# Sheet1.net
KiCad netlist of a schematic drawn in Altium Designer
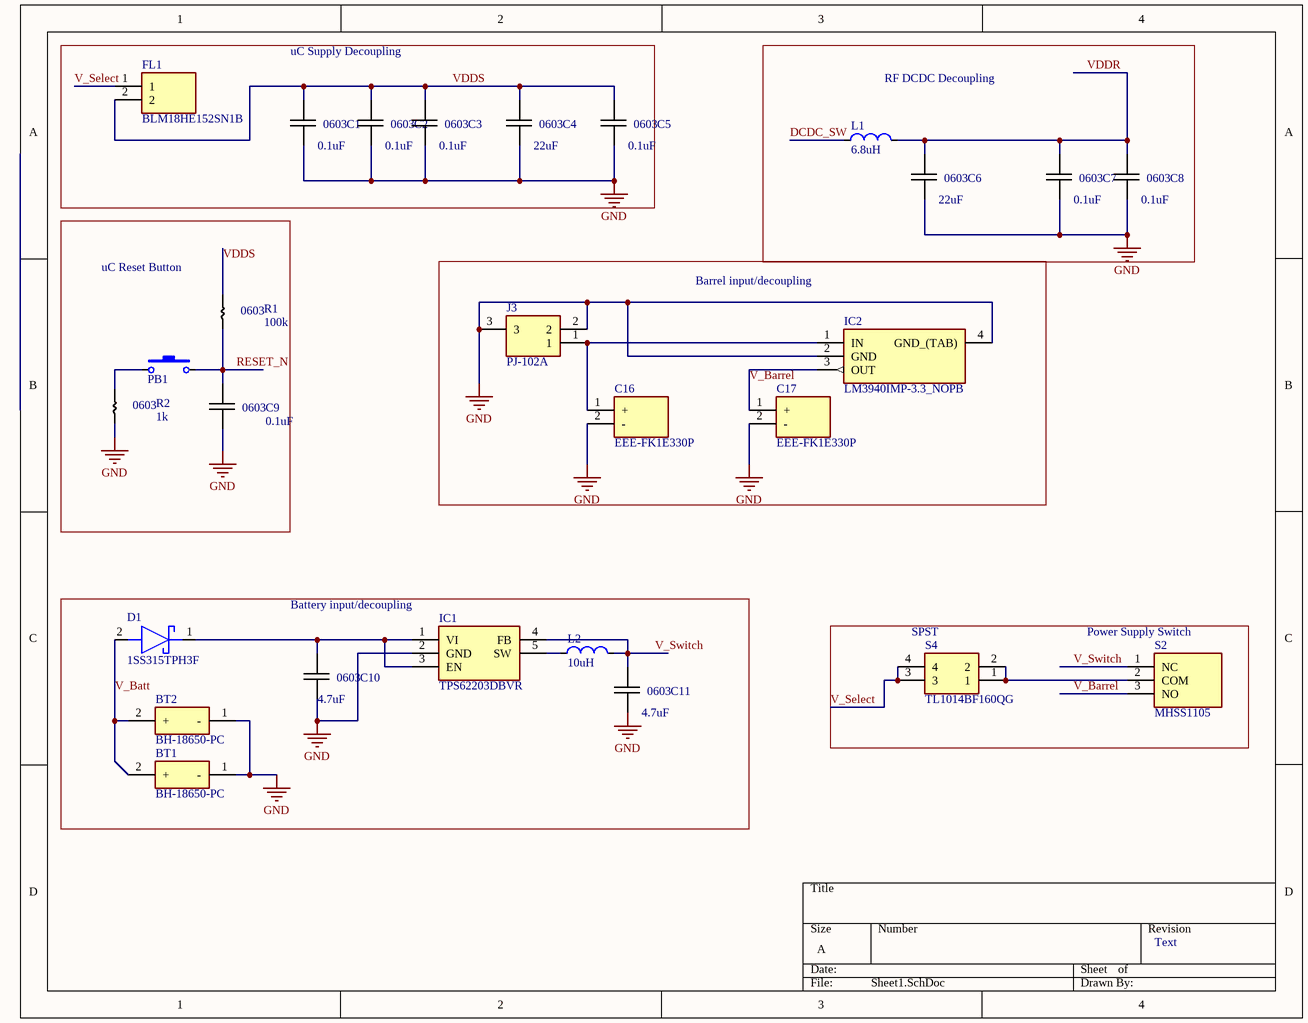
[diagram p0: Sheet1.SchDoc]

(export (version "E")
  (design (tool "Eeschema 10.0.6"))
  (components
    (comp (ref "BT1")
      (value "BH-18650-PC")
      (footprint "BH18650PC")
      (description "Battery")
      (libsource (lib "Enviornmental_Sensor") (part "BH-18650-PC"))
    )
    (comp (ref "BT2")
      (value "BH-18650-PC")
      (footprint "BH18650PC")
      (description "Battery")
      (libsource (lib "Enviornmental_Sensor") (part "BH-18650-PC"))
    )
    (comp (ref "C1")
      (value "0.1uF")
      (footprint "0603_SMD")
      (libsource (lib "Enviornmental_Sensor") (part "C_0603"))
    )
    (comp (ref "C2")
      (value "0.1uF")
      (footprint "0603_SMD")
      (libsource (lib "Enviornmental_Sensor") (part "C_0603"))
    )
    (comp (ref "C3")
      (value "0.1uF")
      (footprint "0603_SMD")
      (libsource (lib "Enviornmental_Sensor") (part "C_0603"))
    )
    (comp (ref "C4")
      (value "22uF")
      (footprint "0603_SMD")
      (libsource (lib "Enviornmental_Sensor") (part "C_0603"))
    )
    (comp (ref "C5")
      (value "0.1uF")
      (footprint "0603_SMD")
      (libsource (lib "Enviornmental_Sensor") (part "C_0603"))
    )
    (comp (ref "C6")
      (value "22uF")
      (footprint "0603_SMD")
      (libsource (lib "Enviornmental_Sensor") (part "C_0603"))
    )
    (comp (ref "C7")
      (value "0.1uF")
      (footprint "0603_SMD")
      (libsource (lib "Enviornmental_Sensor") (part "C_0603"))
    )
    (comp (ref "C8")
      (value "0.1uF")
      (footprint "0603_SMD")
      (libsource (lib "Enviornmental_Sensor") (part "C_0603"))
    )
    (comp (ref "C9")
      (value "0.1uF")
      (footprint "0603_SMD")
      (libsource (lib "Enviornmental_Sensor") (part "C_0603"))
    )
    (comp (ref "C10")
      (value "4.7uF")
      (footprint "0603_SMD")
      (libsource (lib "Enviornmental_Sensor") (part "C_0603"))
    )
    (comp (ref "C11")
      (value "4.7uF")
      (footprint "0603_SMD")
      (libsource (lib "Enviornmental_Sensor") (part "C_0603"))
    )
    (comp (ref "C16")
      (value "EEE-FK1E330P")
      (footprint "SamacSys:CAPAE660X610N")
      (description "Capacitor Polarised")
      (fields (field (name "MOUSER PART NUMBER") "667-EEE-FK1E330P"))
      (libsource (lib "*") (part "EEE-FK1E330P"))
    )
    (comp (ref "C17")
      (value "EEE-FK1E330P")
      (footprint "SamacSys:CAPAE660X610N")
      (description "Capacitor Polarised")
      (fields (field (name "MOUSER PART NUMBER") "667-EEE-FK1E330P"))
      (libsource (lib "*") (part "EEE-FK1E330P"))
    )
    (comp (ref "D1")
      (value "1SS315TPH3F")
      (footprint "SamacSys:SOD2513X110N")
      (description "Schottky Diode")
      (fields (field (name "MOUSER PART NUMBER") "757-1SS315TPH3F"))
      (libsource (lib "*") (part "1SS315TPH3F"))
    )
    (comp (ref "FL1")
      (value "BLM18HE152SN1B")
      (footprint "SamacSys:BEADC1608X95N")
      (description "Filter")
      (libsource (lib "*") (part "BLM18HE152SN1B"))
    )
    (comp (ref "IC1")
      (value "TPS62203DBVR")
      (footprint "SamacSys:SOT95P280X145-5N")
      (description "Integrated Circuit")
      (fields (field (name "MOUSER PART NUMBER") "595-TPS62203DBVR"))
      (libsource (lib "*") (part "TPS62203DBVR"))
    )
    (comp (ref "IC2")
      (value "LM3940IMP-3.3_NOPB")
      (footprint "SamacSys:SOT230P700X180-4N")
      (description "Integrated Circuit")
      (fields
        (field (name "MANUFACTURER_PART_NUMBER") "LM3940IMP-3.3/NOPB")
        (field (name "MOUSER PART NUMBER") "926-LM3940IMP3.3NOPB")
      )
      (libsource (lib "*") (part "LM3940IMP-3.3_NOPB"))
    )
    (comp (ref "J3")
      (value "PJ-102A")
      (footprint "PJ-102AH")
      (description "Connector")
      (fields (field (name "MOUSER PART NUMBER") "490-PJ-102A"))
      (libsource (lib "EnvironmentalSensor") (part "PJ-102A"))
    )
    (comp (ref "L1")
      (value "6.8uH")
      (footprint "PASSIVE-INDUCTOR-0603")
      (description "Generic Inductor")
      (fields (field (name "Comment") "Passive-Inductor (Generic)"))
      (libsource (lib "MasterLib") (part "Passive-Inductor (Generic)"))
    )
    (comp (ref "L2")
      (value "10uH")
      (footprint "PASSIVE-INDUCTOR-0603")
      (description "Generic Inductor")
      (fields (field (name "Comment") "Passive-Inductor (Generic)"))
      (libsource (lib "MasterLib") (part "Passive-Inductor (Generic)"))
    )
    (comp (ref "PB1")
      (value "Interface-Push-Button")
      (footprint "INTERFACE-PUSH-BUTTON")
      (description "2.5mm Tall, 2.5N Force, Straight, SMD, Push Button")
      (fields
        (field (name "MANUFACTURER") "C&K Components")
        (field (name "MANUFACTURER PART NUMBER") "PTS820 J25K SMTR LFS")
      )
      (libsource (lib "MasterLib") (part "Interface-Push-Button"))
    )
    (comp (ref "R1")
      (value "100k")
      (footprint "0603_SMD")
      (libsource (lib "Enviornmental_Sensor") (part "R_0603"))
    )
    (comp (ref "R2")
      (value "1k")
      (footprint "0603_SMD")
      (libsource (lib "Enviornmental_Sensor") (part "R_0603"))
    )
    (comp (ref "S2")
      (value "MHSS1105")
      (footprint "SamacSys:MHSS1105")
      (description "Switch")
      (fields (field (name "MOUSER PART NUMBER") "642-MHSS1105"))
      (libsource (lib "*") (part "MHSS1105"))
    )
    (comp (ref "S4")
      (value "TL1014BF160QG")
      (footprint "SamacSys:TL1014BF160QG")
      (description "Switch")
      (fields (field (name "MOUSER PART NUMBER") "612-TL1014BF160QG"))
      (libsource (lib "*") (part "TL1014BF160QG"))
    )
  )
  (nets
    (net (code "1") (name "/DCDC_SW") (class "Default")
      (node (ref "L1") (pin "1") (pinfunction "1_1") (pintype "passive"))
    )
    (net (code "2") (name "/RESET_N") (class "Default")
      (node (ref "C9") (pin "2") (pinfunction "2_2") (pintype "passive"))
      (node (ref "PB1") (pin "2") (pinfunction "2_2") (pintype "passive"))
      (node (ref "R1") (pin "2") (pinfunction "2_2") (pintype "passive"))
    )
    (net (code "3") (name "/VDDR") (class "Default")
      (node (ref "C6") (pin "2") (pinfunction "2_2") (pintype "passive"))
      (node (ref "C7") (pin "2") (pinfunction "2_2") (pintype "passive"))
      (node (ref "C8") (pin "2") (pinfunction "2_2") (pintype "passive"))
      (node (ref "L1") (pin "2") (pinfunction "2_2") (pintype "passive"))
    )
    (net (code "4") (name "/VDDS") (class "Default")
      (node (ref "C1") (pin "2") (pinfunction "2_2") (pintype "passive"))
      (node (ref "C2") (pin "2") (pinfunction "2_2") (pintype "passive"))
      (node (ref "C3") (pin "2") (pinfunction "2_2") (pintype "passive"))
      (node (ref "C4") (pin "2") (pinfunction "2_2") (pintype "passive"))
      (node (ref "C5") (pin "2") (pinfunction "2_2") (pintype "passive"))
      (node (ref "FL1") (pin "2") (pinfunction "2_2") (pintype "passive"))
      (node (ref "R1") (pin "1") (pinfunction "1_1") (pintype "passive"))
    )
    (net (code "5") (name "/V_Barrel") (class "Default")
      (node (ref "C17") (pin "1") (pinfunction "+_1") (pintype "passive"))
      (node (ref "IC2") (pin "3") (pinfunction "OUT_3") (pintype "output"))
      (node (ref "S2") (pin "3") (pinfunction "NO_3") (pintype "passive"))
    )
    (net (code "6") (name "/V_Batt") (class "Default")
      (node (ref "BT1") (pin "2") (pinfunction "+_2") (pintype "passive"))
      (node (ref "BT2") (pin "2") (pinfunction "+_2") (pintype "passive"))
      (node (ref "D1") (pin "2") (pinfunction "A_2") (pintype "passive"))
    )
    (net (code "7") (name "/V_Select") (class "Default")
      (node (ref "FL1") (pin "1") (pinfunction "1_1") (pintype "passive"))
      (node (ref "S4") (pin "3") (pinfunction "3_3") (pintype "passive"))
      (node (ref "S4") (pin "4") (pinfunction "4_4") (pintype "passive"))
    )
    (net (code "8") (name "/V_Switch") (class "Default")
      (node (ref "C11") (pin "2") (pinfunction "2_2") (pintype "passive"))
      (node (ref "IC1") (pin "4") (pinfunction "FB_4") (pintype "passive"))
      (node (ref "L2") (pin "2") (pinfunction "2_2") (pintype "passive"))
      (node (ref "S2") (pin "1") (pinfunction "NC_1") (pintype "passive"))
    )
    (net (code "9") (name "GND") (class "Default")
      (node (ref "BT1") (pin "1") (pinfunction "-_1") (pintype "passive"))
      (node (ref "BT2") (pin "1") (pinfunction "-_1") (pintype "passive"))
      (node (ref "C1") (pin "1") (pinfunction "1_1") (pintype "passive"))
      (node (ref "C10") (pin "1") (pinfunction "1_1") (pintype "passive"))
      (node (ref "C11") (pin "1") (pinfunction "1_1") (pintype "passive"))
      (node (ref "C16") (pin "2") (pinfunction "-_2") (pintype "passive"))
      (node (ref "C17") (pin "2") (pinfunction "-_2") (pintype "passive"))
      (node (ref "C2") (pin "1") (pinfunction "1_1") (pintype "passive"))
      (node (ref "C3") (pin "1") (pinfunction "1_1") (pintype "passive"))
      (node (ref "C4") (pin "1") (pinfunction "1_1") (pintype "passive"))
      (node (ref "C5") (pin "1") (pinfunction "1_1") (pintype "passive"))
      (node (ref "C6") (pin "1") (pinfunction "1_1") (pintype "passive"))
      (node (ref "C7") (pin "1") (pinfunction "1_1") (pintype "passive"))
      (node (ref "C8") (pin "1") (pinfunction "1_1") (pintype "passive"))
      (node (ref "C9") (pin "1") (pinfunction "1_1") (pintype "passive"))
      (node (ref "IC1") (pin "2") (pinfunction "GND_2") (pintype "passive"))
      (node (ref "IC2") (pin "2") (pinfunction "GND_2") (pintype "power_in"))
      (node (ref "IC2") (pin "4") (pinfunction "GND_(TAB)_4") (pintype "power_in"))
      (node (ref "J3") (pin "2") (pinfunction "2_2") (pintype "passive"))
      (node (ref "J3") (pin "3") (pinfunction "3_3") (pintype "passive"))
      (node (ref "R2") (pin "2") (pinfunction "2_2") (pintype "passive"))
    )
    (net (code "10") (name "Net-(C16-+)") (class "Default")
      (node (ref "C16") (pin "1") (pinfunction "+_1") (pintype "passive"))
      (node (ref "IC2") (pin "1") (pinfunction "IN_1") (pintype "power_in"))
      (node (ref "J3") (pin "1") (pinfunction "1_1") (pintype "passive"))
    )
    (net (code "11") (name "Net-(D1-K)") (class "Default")
      (node (ref "C10") (pin "2") (pinfunction "2_2") (pintype "passive"))
      (node (ref "D1") (pin "1") (pinfunction "K_1") (pintype "passive"))
      (node (ref "IC1") (pin "1") (pinfunction "VI_1") (pintype "passive"))
      (node (ref "IC1") (pin "3") (pinfunction "EN_3") (pintype "passive"))
    )
    (net (code "12") (name "Net-(IC1-SW)") (class "Default")
      (node (ref "IC1") (pin "5") (pinfunction "SW_5") (pintype "passive"))
      (node (ref "L2") (pin "1") (pinfunction "1_1") (pintype "passive"))
    )
    (net (code "13") (name "Net-(PB1-Pad1)") (class "Default")
      (node (ref "PB1") (pin "1") (pinfunction "1_1") (pintype "passive"))
      (node (ref "R2") (pin "1") (pinfunction "1_1") (pintype "passive"))
    )
    (net (code "14") (name "Net-(S2-COM)") (class "Default")
      (node (ref "S2") (pin "2") (pinfunction "COM_2") (pintype "passive"))
      (node (ref "S4") (pin "1") (pinfunction "1_1") (pintype "passive"))
      (node (ref "S4") (pin "2") (pinfunction "2_2") (pintype "passive"))
    )
  )
)
